# esquematicoOPTO.net
KiCad netlist of a schematic drawn in Altium Designer
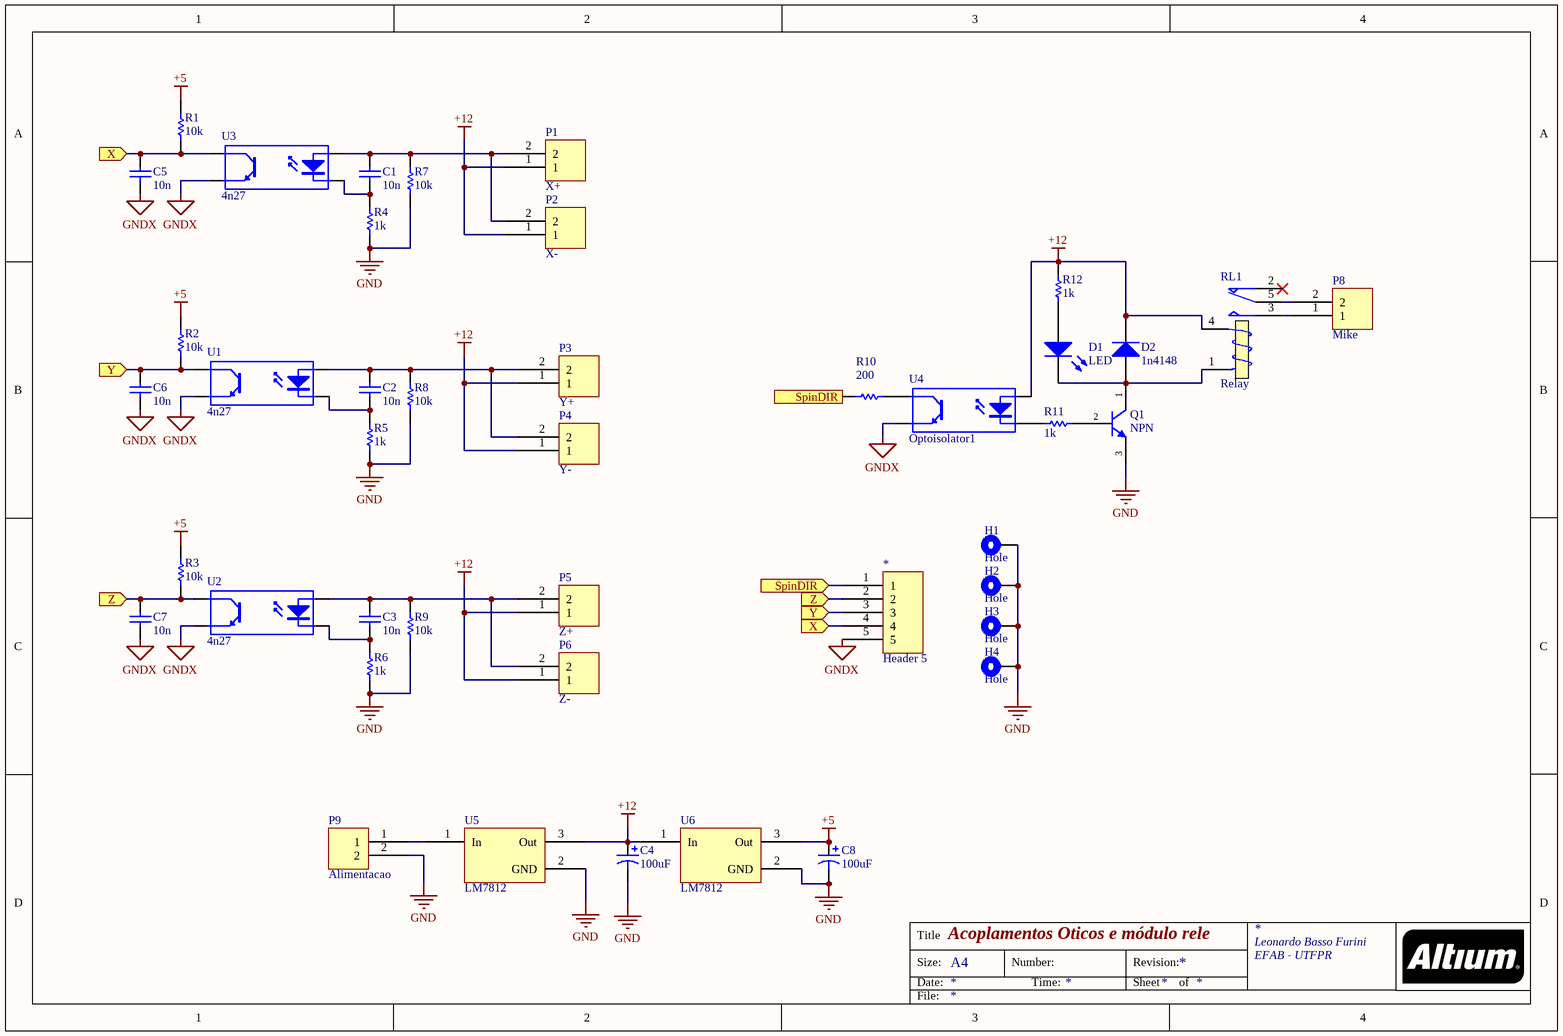
[diagram p0: esquematicoOPTO.SchDoc]

(export (version "E")
  (design (tool "Eeschema 10.0.6"))
  (components
    (comp (ref "*")
      (value "Header 5")
      (footprint "HDR1x5M")
      (libsource (lib "Connectores") (part "Header 5"))
    )
    (comp (ref "C1")
      (value "10n")
      (footprint "Capaciotrpoliester")
      (description "Capacitor")
      (libsource (lib "Basic Library") (part "C"))
    )
    (comp (ref "C2")
      (value "10n")
      (footprint "Capaciotrpoliester")
      (description "Capacitor")
      (libsource (lib "Basic Library") (part "C"))
    )
    (comp (ref "C3")
      (value "10n")
      (footprint "Capaciotrpoliester")
      (description "Capacitor")
      (libsource (lib "Basic Library") (part "C"))
    )
    (comp (ref "C4")
      (value "100uF")
      (footprint "cap_rad_d6.3X11POL")
      (description "Polarized Capacitor")
      (libsource (lib "Basic Library") (part "CP"))
    )
    (comp (ref "C5")
      (value "10n")
      (footprint "RAD-0.2")
      (description "Capacitor")
      (libsource (lib "Basic Library") (part "C"))
    )
    (comp (ref "C6")
      (value "10n")
      (footprint "RAD-0.2")
      (description "Capacitor")
      (libsource (lib "Basic Library") (part "C"))
    )
    (comp (ref "C7")
      (value "10n")
      (footprint "RAD-0.2")
      (description "Capacitor")
      (libsource (lib "Basic Library") (part "C"))
    )
    (comp (ref "C8")
      (value "100uF")
      (footprint "cap_rad_d6.3X11POL")
      (description "Polarized Capacitor")
      (libsource (lib "Basic Library") (part "CP"))
    )
    (comp (ref "D1") (value "LED") (footprint "LED_5MM_GREEN") (libsource (lib "Basic Library") (part "LED")))
    (comp (ref "D2")
      (value "1n4148")
      (footprint "Diodo")
      (description "Diode")
      (libsource (lib "Basic Library") (part "D"))
    )
    (comp (ref "H1") (value "Hole") (footprint "HOLE_M2") (libsource (lib "Basic Library") (part "Hole")))
    (comp (ref "H2") (value "Hole") (footprint "HOLE_M2") (libsource (lib "Basic Library") (part "Hole")))
    (comp (ref "H3") (value "Hole") (footprint "HOLE_M2") (libsource (lib "Basic Library") (part "Hole")))
    (comp (ref "H4") (value "Hole") (footprint "HOLE_M2") (libsource (lib "Basic Library") (part "Hole")))
    (comp (ref "P1") (value "X+") (footprint "KRE-2") (libsource (lib "Connectores") (part "Header 2")))
    (comp (ref "P2") (value "X-") (footprint "KRE-2") (libsource (lib "Connectores") (part "Header 2")))
    (comp (ref "P3") (value "Y+") (footprint "KRE-2") (libsource (lib "Connectores") (part "Header 2")))
    (comp (ref "P4") (value "Y-") (footprint "KRE-2") (libsource (lib "Connectores") (part "Header 2")))
    (comp (ref "P5") (value "Z+") (footprint "KRE-2") (libsource (lib "Connectores") (part "Header 2")))
    (comp (ref "P6") (value "Z-") (footprint "KRE-2") (libsource (lib "Connectores") (part "Header 2")))
    (comp (ref "P8") (value "Mike") (footprint "KRE-2") (libsource (lib "Connectores") (part "Header 2")))
    (comp (ref "P9") (value "Alimentacao") (footprint "KRE-2") (libsource (lib "") (part "Header 2_1")))
    (comp (ref "Q1")
      (value "NPN")
      (footprint "TO-92")
      (description "NPN Bipolar Transistor")
      (libsource (lib "Basic Library") (part "NPN"))
    )
    (comp (ref "R1")
      (value "10k")
      (footprint "AXIAL-0.4")
      (description "Resistor")
      (libsource (lib "Basic Library") (part "R"))
    )
    (comp (ref "R2")
      (value "10k")
      (footprint "AXIAL-0.4")
      (description "Resistor")
      (libsource (lib "Basic Library") (part "R"))
    )
    (comp (ref "R3")
      (value "10k")
      (footprint "AXIAL-0.4")
      (description "Resistor")
      (libsource (lib "Basic Library") (part "R"))
    )
    (comp (ref "R4")
      (value "1k")
      (footprint "AXIAL-0.4")
      (description "Resistor")
      (libsource (lib "Basic Library") (part "R"))
    )
    (comp (ref "R5")
      (value "1k")
      (footprint "AXIAL-0.4")
      (description "Resistor")
      (libsource (lib "Basic Library") (part "R"))
    )
    (comp (ref "R6")
      (value "1k")
      (footprint "AXIAL-0.4")
      (description "Resistor")
      (libsource (lib "Basic Library") (part "R"))
    )
    (comp (ref "R7")
      (value "10k")
      (footprint "AXIAL-0.4")
      (description "Resistor")
      (libsource (lib "Basic Library") (part "R"))
    )
    (comp (ref "R8")
      (value "10k")
      (footprint "AXIAL-0.4")
      (description "Resistor")
      (libsource (lib "Basic Library") (part "R"))
    )
    (comp (ref "R9")
      (value "10k")
      (footprint "AXIAL-0.4")
      (description "Resistor")
      (libsource (lib "Basic Library") (part "R"))
    )
    (comp (ref "R10")
      (value "200")
      (footprint "AXIAL-0.4")
      (description "Resistor")
      (libsource (lib "Basic Library") (part "R"))
    )
    (comp (ref "R11")
      (value "1k")
      (footprint "AXIAL-0.4")
      (description "Resistor")
      (libsource (lib "Basic Library") (part "R"))
    )
    (comp (ref "R12")
      (value "1k")
      (footprint "AXIAL-0.4")
      (description "Resistor")
      (libsource (lib "Basic Library") (part "R"))
    )
    (comp (ref "RL1")
      (value "Relay")
      (footprint "FINDER-36.11")
      (description "SPDT Relay")
      (libsource (lib "Basic Library") (part "Relay"))
    )
    (comp (ref "U1")
      (value "4n27")
      (footprint "DIP-6")
      (description "4-Pin Phototransistor Optocoupler")
      (libsource (lib "Basic Library") (part "Optoisolator1"))
    )
    (comp (ref "U2")
      (value "4n27")
      (footprint "DIP-6")
      (description "4-Pin Phototransistor Optocoupler")
      (libsource (lib "Basic Library") (part "Optoisolator1"))
    )
    (comp (ref "U3")
      (value "4n27")
      (footprint "DIP-6")
      (description "4-Pin Phototransistor Optocoupler")
      (libsource (lib "Basic Library") (part "Optoisolator1"))
    )
    (comp (ref "U4")
      (value "Optoisolator1")
      (footprint "DIP-6")
      (description "4-Pin Phototransistor Optocoupler")
      (libsource (lib "Basic Library") (part "Optoisolator1"))
    )
    (comp (ref "U5") (value "LM7812") (footprint "LM7805") (libsource (lib "BateriaLIB") (part "LM7805")))
    (comp (ref "U6") (value "LM7812") (footprint "LM7805") (libsource (lib "BateriaLIB") (part "LM7805")))
  )
  (nets
    (net (code "1") (name "+5") (class "Default")
      (node (ref "C8") (pin "1") (pinfunction "1_1") (pintype "passive"))
      (node (ref "R1") (pin "2") (pinfunction "2_2") (pintype "passive"))
      (node (ref "R2") (pin "2") (pinfunction "2_2") (pintype "passive"))
      (node (ref "R3") (pin "2") (pinfunction "2_2") (pintype "passive"))
      (node (ref "U6") (pin "3") (pinfunction "Out_3") (pintype "passive"))
    )
    (net (code "2") (name "+12") (class "Default")
      (node (ref "C4") (pin "1") (pinfunction "1_1") (pintype "passive"))
      (node (ref "D2") (pin "2") (pinfunction "K_2") (pintype "passive"))
      (node (ref "P1") (pin "1") (pinfunction "1_1") (pintype "passive"))
      (node (ref "P2") (pin "1") (pinfunction "1_1") (pintype "passive"))
      (node (ref "P3") (pin "1") (pinfunction "1_1") (pintype "passive"))
      (node (ref "P4") (pin "1") (pinfunction "1_1") (pintype "passive"))
      (node (ref "P5") (pin "1") (pinfunction "1_1") (pintype "passive"))
      (node (ref "P6") (pin "1") (pinfunction "1_1") (pintype "passive"))
      (node (ref "R12") (pin "2") (pinfunction "2_2") (pintype "passive"))
      (node (ref "RL1") (pin "4") (pinfunction "T1_4") (pintype "passive"))
      (node (ref "U4") (pin "1") (pinfunction "A_1") (pintype "passive"))
      (node (ref "U5") (pin "3") (pinfunction "Out_3") (pintype "passive"))
      (node (ref "U6") (pin "1") (pinfunction "In_1") (pintype "passive"))
    )
    (net (code "3") (name "/SpinDIR") (class "Default")
      (node (ref "*") (pin "1") (pinfunction "1_1") (pintype "passive"))
      (node (ref "R10") (pin "2") (pinfunction "2_2") (pintype "passive"))
    )
    (net (code "4") (name "/X") (class "Default")
      (node (ref "*") (pin "4") (pinfunction "4_4") (pintype "passive"))
      (node (ref "C5") (pin "2") (pinfunction "2_2") (pintype "passive"))
      (node (ref "R1") (pin "1") (pinfunction "1_1") (pintype "passive"))
      (node (ref "U3") (pin "4") (pinfunction "C_4") (pintype "passive"))
    )
    (net (code "5") (name "/Y") (class "Default")
      (node (ref "*") (pin "3") (pinfunction "3_3") (pintype "passive"))
      (node (ref "C6") (pin "2") (pinfunction "2_2") (pintype "passive"))
      (node (ref "R2") (pin "1") (pinfunction "1_1") (pintype "passive"))
      (node (ref "U1") (pin "4") (pinfunction "C_4") (pintype "passive"))
    )
    (net (code "6") (name "/Z") (class "Default")
      (node (ref "*") (pin "2") (pinfunction "2_2") (pintype "passive"))
      (node (ref "C7") (pin "2") (pinfunction "2_2") (pintype "passive"))
      (node (ref "R3") (pin "1") (pinfunction "1_1") (pintype "passive"))
      (node (ref "U2") (pin "4") (pinfunction "C_4") (pintype "passive"))
    )
    (net (code "7") (name "GND") (class "Default")
      (node (ref "C4") (pin "2") (pinfunction "2_2") (pintype "passive"))
      (node (ref "C8") (pin "2") (pinfunction "2_2") (pintype "passive"))
      (node (ref "H1") (pin "1") (pinfunction "1_1") (pintype "passive"))
      (node (ref "H2") (pin "1") (pinfunction "1_1") (pintype "passive"))
      (node (ref "H3") (pin "1") (pinfunction "1_1") (pintype "passive"))
      (node (ref "H4") (pin "1") (pinfunction "1_1") (pintype "passive"))
      (node (ref "P9") (pin "2") (pinfunction "2_2") (pintype "passive"))
      (node (ref "Q1") (pin "3") (pinfunction "E_3") (pintype "passive"))
      (node (ref "R4") (pin "1") (pinfunction "1_1") (pintype "passive"))
      (node (ref "R5") (pin "1") (pinfunction "1_1") (pintype "passive"))
      (node (ref "R6") (pin "1") (pinfunction "1_1") (pintype "passive"))
      (node (ref "R7") (pin "2") (pinfunction "2_2") (pintype "passive"))
      (node (ref "R8") (pin "2") (pinfunction "2_2") (pintype "passive"))
      (node (ref "R9") (pin "2") (pinfunction "2_2") (pintype "passive"))
      (node (ref "U5") (pin "2") (pinfunction "GND_2") (pintype "passive"))
      (node (ref "U6") (pin "2") (pinfunction "GND_2") (pintype "passive"))
    )
    (net (code "8") (name "GNDX") (class "Default")
      (node (ref "*") (pin "5") (pinfunction "5_5") (pintype "passive"))
      (node (ref "C5") (pin "1") (pinfunction "1_1") (pintype "passive"))
      (node (ref "C6") (pin "1") (pinfunction "1_1") (pintype "passive"))
      (node (ref "C7") (pin "1") (pinfunction "1_1") (pintype "passive"))
      (node (ref "U1") (pin "3") (pinfunction "E_3") (pintype "passive"))
      (node (ref "U2") (pin "3") (pinfunction "E_3") (pintype "passive"))
      (node (ref "U3") (pin "3") (pinfunction "E_3") (pintype "passive"))
      (node (ref "U4") (pin "3") (pinfunction "E_3") (pintype "passive"))
    )
    (net (code "9") (name "Net-(D1-A)") (class "Default")
      (node (ref "D1") (pin "1") (pinfunction "A_1") (pintype "passive"))
      (node (ref "R12") (pin "1") (pinfunction "1_1") (pintype "passive"))
    )
    (net (code "10") (name "Net-(D1-K)") (class "Default")
      (node (ref "D1") (pin "2") (pinfunction "K_2") (pintype "passive"))
      (node (ref "D2") (pin "1") (pinfunction "A_1") (pintype "passive"))
      (node (ref "Q1") (pin "1") (pinfunction "C_1") (pintype "passive"))
      (node (ref "RL1") (pin "1") (pinfunction "T2_1") (pintype "passive"))
    )
    (net (code "11") (name "Net-(Q1-B)") (class "Default")
      (node (ref "Q1") (pin "2") (pinfunction "B_2") (pintype "passive"))
      (node (ref "R11") (pin "1") (pinfunction "1_1") (pintype "passive"))
    )
    (net (code "12") (name "Net-(RL1-COM)") (class "Default")
      (node (ref "P8") (pin "2") (pinfunction "2_2") (pintype "passive"))
      (node (ref "RL1") (pin "5") (pinfunction "COM_5") (pintype "passive"))
    )
    (net (code "13") (name "Net-(RL1-NO)") (class "Default")
      (node (ref "P8") (pin "1") (pinfunction "1_1") (pintype "passive"))
      (node (ref "RL1") (pin "3") (pinfunction "NO_3") (pintype "passive"))
    )
    (net (code "14") (name "Net-(U1-A)") (class "Default")
      (node (ref "C2") (pin "2") (pinfunction "2_2") (pintype "passive"))
      (node (ref "P3") (pin "2") (pinfunction "2_2") (pintype "passive"))
      (node (ref "P4") (pin "2") (pinfunction "2_2") (pintype "passive"))
      (node (ref "R8") (pin "1") (pinfunction "1_1") (pintype "passive"))
      (node (ref "U1") (pin "1") (pinfunction "A_1") (pintype "passive"))
    )
    (net (code "15") (name "Net-(U1-K)") (class "Default")
      (node (ref "C2") (pin "1") (pinfunction "1_1") (pintype "passive"))
      (node (ref "R5") (pin "2") (pinfunction "2_2") (pintype "passive"))
      (node (ref "U1") (pin "2") (pinfunction "K_2") (pintype "passive"))
    )
    (net (code "16") (name "Net-(U2-A)") (class "Default")
      (node (ref "C3") (pin "2") (pinfunction "2_2") (pintype "passive"))
      (node (ref "P5") (pin "2") (pinfunction "2_2") (pintype "passive"))
      (node (ref "P6") (pin "2") (pinfunction "2_2") (pintype "passive"))
      (node (ref "R9") (pin "1") (pinfunction "1_1") (pintype "passive"))
      (node (ref "U2") (pin "1") (pinfunction "A_1") (pintype "passive"))
    )
    (net (code "17") (name "Net-(U2-K)") (class "Default")
      (node (ref "C3") (pin "1") (pinfunction "1_1") (pintype "passive"))
      (node (ref "R6") (pin "2") (pinfunction "2_2") (pintype "passive"))
      (node (ref "U2") (pin "2") (pinfunction "K_2") (pintype "passive"))
    )
    (net (code "18") (name "Net-(U3-A)") (class "Default")
      (node (ref "C1") (pin "2") (pinfunction "2_2") (pintype "passive"))
      (node (ref "P1") (pin "2") (pinfunction "2_2") (pintype "passive"))
      (node (ref "P2") (pin "2") (pinfunction "2_2") (pintype "passive"))
      (node (ref "R7") (pin "1") (pinfunction "1_1") (pintype "passive"))
      (node (ref "U3") (pin "1") (pinfunction "A_1") (pintype "passive"))
    )
    (net (code "19") (name "Net-(U3-K)") (class "Default")
      (node (ref "C1") (pin "1") (pinfunction "1_1") (pintype "passive"))
      (node (ref "R4") (pin "2") (pinfunction "2_2") (pintype "passive"))
      (node (ref "U3") (pin "2") (pinfunction "K_2") (pintype "passive"))
    )
    (net (code "20") (name "Net-(U4-C)") (class "Default")
      (node (ref "R10") (pin "1") (pinfunction "1_1") (pintype "passive"))
      (node (ref "U4") (pin "4") (pinfunction "C_4") (pintype "passive"))
    )
    (net (code "21") (name "Net-(U4-K)") (class "Default")
      (node (ref "R11") (pin "2") (pinfunction "2_2") (pintype "passive"))
      (node (ref "U4") (pin "2") (pinfunction "K_2") (pintype "passive"))
    )
    (net (code "22") (name "Net-(U5-In)") (class "Default")
      (node (ref "P9") (pin "1") (pinfunction "1_1") (pintype "passive"))
      (node (ref "U5") (pin "1") (pinfunction "In_1") (pintype "passive"))
    )
    (net (code "23") (name "unconnected-(RL1-NC-Pad2)") (class "Default")
      (node (ref "RL1") (pin "2") (pinfunction "NC_2") (pintype "passive+no_connect"))
    )
  )
)
